# cv-strip.net
KiCad netlist of a schematic drawn in EAGLE
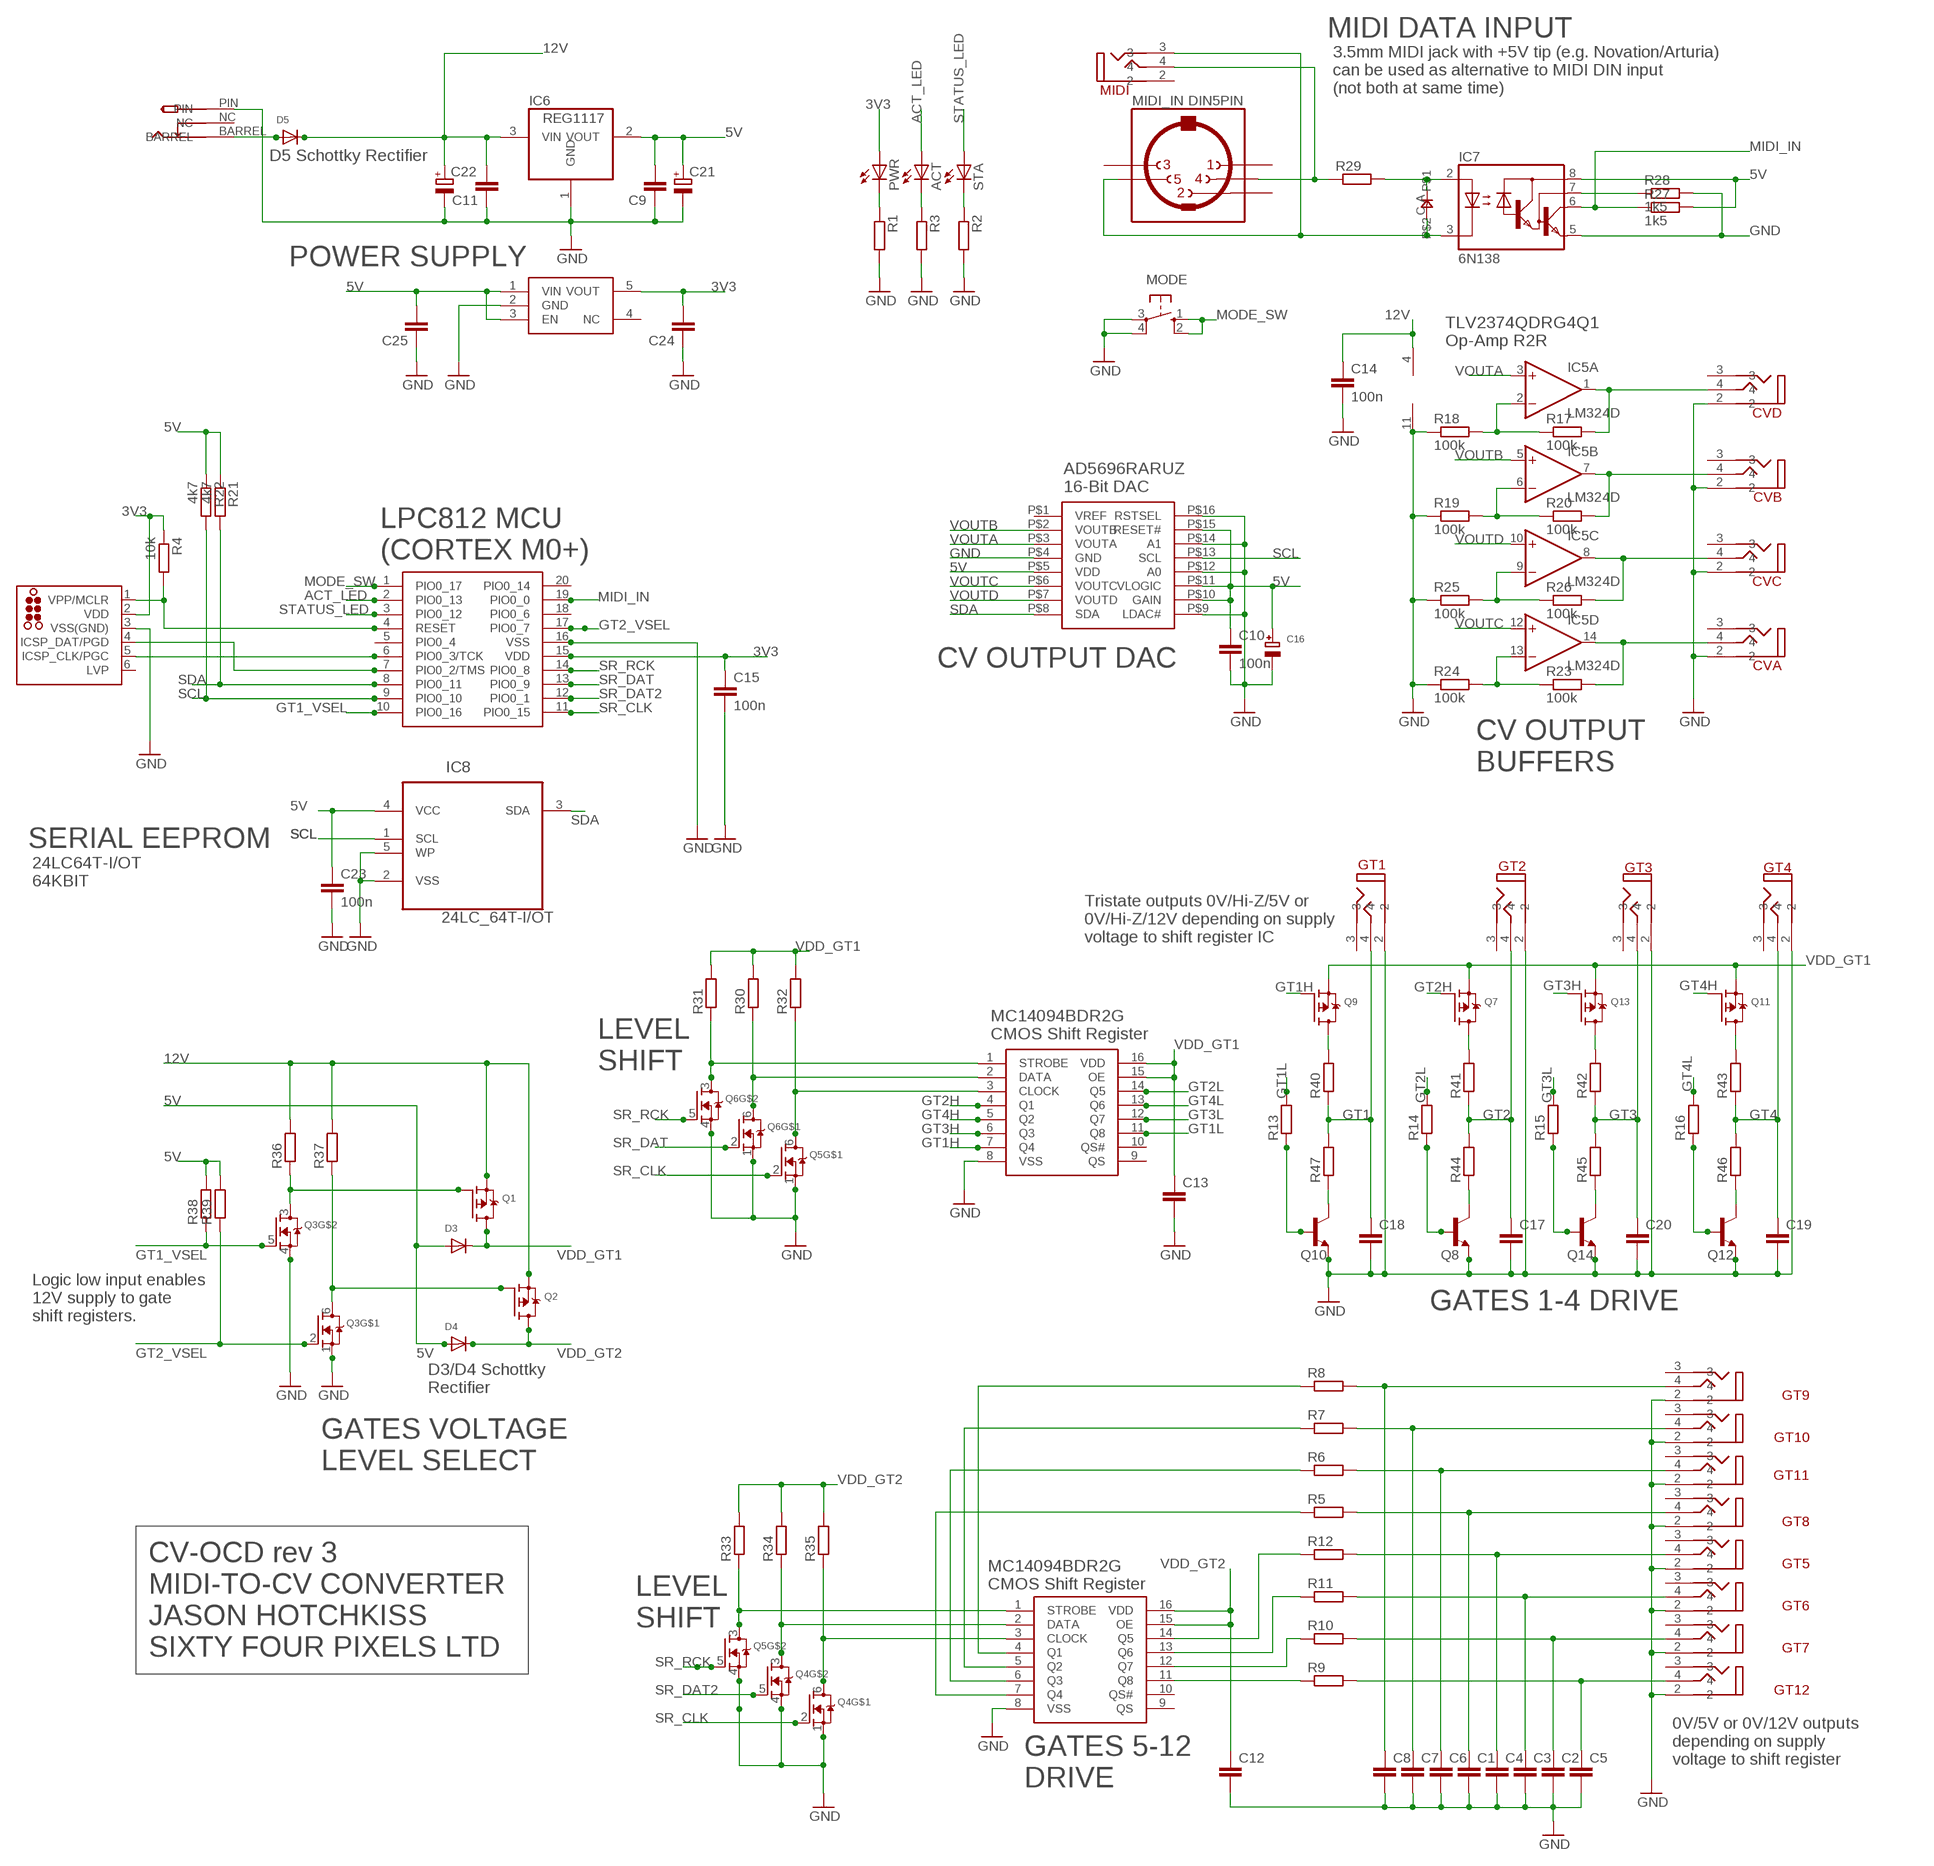
[diagram p0: schematic, sheet 1]

(export (version "E")
  (design (tool "Eeschema 10.0.6"))
  (components
    (comp (ref "ACT")
      (value "LED3MM")
      (footprint "eagle-import:LED3MM")
      (libsource (lib "eagle-import") (part "LED3MM"))
    )
    (comp (ref "C1")
      (value "C-EUC0805")
      (footprint "eagle-import:C0805")
      (libsource (lib "eagle-import") (part "C-EUC0805"))
    )
    (comp (ref "C2")
      (value "C-EUC0805")
      (footprint "eagle-import:C0805")
      (libsource (lib "eagle-import") (part "C-EUC0805"))
    )
    (comp (ref "C3")
      (value "C-EUC0805")
      (footprint "eagle-import:C0805")
      (libsource (lib "eagle-import") (part "C-EUC0805"))
    )
    (comp (ref "C4")
      (value "C-EUC0805")
      (footprint "eagle-import:C0805")
      (libsource (lib "eagle-import") (part "C-EUC0805"))
    )
    (comp (ref "C5")
      (value "C-EUC0805")
      (footprint "eagle-import:C0805")
      (libsource (lib "eagle-import") (part "C-EUC0805"))
    )
    (comp (ref "C6")
      (value "C-EUC0805")
      (footprint "eagle-import:C0805")
      (libsource (lib "eagle-import") (part "C-EUC0805"))
    )
    (comp (ref "C7")
      (value "C-EUC0805")
      (footprint "eagle-import:C0805")
      (libsource (lib "eagle-import") (part "C-EUC0805"))
    )
    (comp (ref "C8")
      (value "C-EUC0805")
      (footprint "eagle-import:C0805")
      (libsource (lib "eagle-import") (part "C-EUC0805"))
    )
    (comp (ref "C9")
      (value "C-EUC0805")
      (footprint "eagle-import:C0805")
      (libsource (lib "eagle-import") (part "C-EUC0805"))
    )
    (comp (ref "C10")
      (value "100n")
      (footprint "eagle-import:C0805")
      (libsource (lib "eagle-import") (part "C-EUC0805"))
    )
    (comp (ref "C11")
      (value "C-EUC0805")
      (footprint "eagle-import:C0805")
      (libsource (lib "eagle-import") (part "C-EUC0805"))
    )
    (comp (ref "C12")
      (value "C-EUC0805")
      (footprint "eagle-import:C0805")
      (libsource (lib "eagle-import") (part "C-EUC0805"))
    )
    (comp (ref "C13")
      (value "C-EUC0805")
      (footprint "eagle-import:C0805")
      (libsource (lib "eagle-import") (part "C-EUC0805"))
    )
    (comp (ref "C14")
      (value "100n")
      (footprint "eagle-import:C0805")
      (libsource (lib "eagle-import") (part "C-EUC0805"))
    )
    (comp (ref "C15")
      (value "100n")
      (footprint "eagle-import:C0805")
      (libsource (lib "eagle-import") (part "C-EUC0805"))
    )
    (comp (ref "C16")
      (value "CAP_TANTALUMA/3216_REFLOW")
      (footprint "eagle-import:EIA3216-18_A-R")
      (libsource (lib "eagle-import") (part "CAP_TANTALUMA/3216_REFLOW"))
    )
    (comp (ref "C17")
      (value "C-EUC0805")
      (footprint "eagle-import:C0805")
      (libsource (lib "eagle-import") (part "C-EUC0805"))
    )
    (comp (ref "C18")
      (value "C-EUC0805")
      (footprint "eagle-import:C0805")
      (libsource (lib "eagle-import") (part "C-EUC0805"))
    )
    (comp (ref "C19")
      (value "C-EUC0805")
      (footprint "eagle-import:C0805")
      (libsource (lib "eagle-import") (part "C-EUC0805"))
    )
    (comp (ref "C20")
      (value "C-EUC0805")
      (footprint "eagle-import:C0805")
      (libsource (lib "eagle-import") (part "C-EUC0805"))
    )
    (comp (ref "C21")
      (value "CPOL-EUE2.5-5")
      (footprint "eagle-import:E2,5-5")
      (libsource (lib "eagle-import") (part "CPOL-EUE2.5-5"))
    )
    (comp (ref "C22")
      (value "CPOL-EUE2.5-5")
      (footprint "eagle-import:E2,5-5")
      (libsource (lib "eagle-import") (part "CPOL-EUE2.5-5"))
    )
    (comp (ref "C23")
      (value "100n")
      (footprint "eagle-import:C0805")
      (libsource (lib "eagle-import") (part "C-EUC0805"))
    )
    (comp (ref "C24")
      (value "C-EUC0805")
      (footprint "eagle-import:C0805")
      (libsource (lib "eagle-import") (part "C-EUC0805"))
    )
    (comp (ref "C25")
      (value "C-EUC0805")
      (footprint "eagle-import:C0805")
      (libsource (lib "eagle-import") (part "C-EUC0805"))
    )
    (comp (ref "CVA")
      (value "VERTICAL_3_5MM_SOCKET")
      (footprint "eagle-import:VERTICAL_3_5MM_SOCKET")
      (libsource (lib "eagle-import") (part "VERTICAL_3_5MM_SOCKET"))
    )
    (comp (ref "CVB")
      (value "VERTICAL_3_5MM_SOCKET")
      (footprint "eagle-import:VERTICAL_3_5MM_SOCKET")
      (libsource (lib "eagle-import") (part "VERTICAL_3_5MM_SOCKET"))
    )
    (comp (ref "CVC")
      (value "VERTICAL_3_5MM_SOCKET")
      (footprint "eagle-import:VERTICAL_3_5MM_SOCKET")
      (libsource (lib "eagle-import") (part "VERTICAL_3_5MM_SOCKET"))
    )
    (comp (ref "CVD")
      (value "VERTICAL_3_5MM_SOCKET")
      (footprint "eagle-import:VERTICAL_3_5MM_SOCKET")
      (libsource (lib "eagle-import") (part "VERTICAL_3_5MM_SOCKET"))
    )
    (comp (ref "D1")
      (value "0805DIODE")
      (footprint "eagle-import:0805DIODE")
      (libsource (lib "eagle-import") (part "0805DIODE"))
    )
    (comp (ref "D3")
      (value "DIODESOD-123")
      (footprint "eagle-import:SOD-123")
      (libsource (lib "eagle-import") (part "DIODESOD-123"))
    )
    (comp (ref "D4")
      (value "DIODESOD-123")
      (footprint "eagle-import:SOD-123")
      (libsource (lib "eagle-import") (part "DIODESOD-123"))
    )
    (comp (ref "D5")
      (value "DIODESOD-123")
      (footprint "eagle-import:SOD-123")
      (libsource (lib "eagle-import") (part "DIODESOD-123"))
    )
    (comp (ref "GT1")
      (value "VERTICAL_3_5MM_SOCKET")
      (footprint "eagle-import:VERTICAL_3_5MM_SOCKET")
      (libsource (lib "eagle-import") (part "VERTICAL_3_5MM_SOCKET"))
    )
    (comp (ref "GT2")
      (value "VERTICAL_3_5MM_SOCKET")
      (footprint "eagle-import:VERTICAL_3_5MM_SOCKET")
      (libsource (lib "eagle-import") (part "VERTICAL_3_5MM_SOCKET"))
    )
    (comp (ref "GT3")
      (value "VERTICAL_3_5MM_SOCKET")
      (footprint "eagle-import:VERTICAL_3_5MM_SOCKET")
      (libsource (lib "eagle-import") (part "VERTICAL_3_5MM_SOCKET"))
    )
    (comp (ref "GT4")
      (value "VERTICAL_3_5MM_SOCKET")
      (footprint "eagle-import:VERTICAL_3_5MM_SOCKET")
      (libsource (lib "eagle-import") (part "VERTICAL_3_5MM_SOCKET"))
    )
    (comp (ref "GT5")
      (value "VERTICAL_3_5MM_SOCKET")
      (footprint "eagle-import:VERTICAL_3_5MM_SOCKET")
      (libsource (lib "eagle-import") (part "VERTICAL_3_5MM_SOCKET"))
    )
    (comp (ref "GT6")
      (value "VERTICAL_3_5MM_SOCKET")
      (footprint "eagle-import:VERTICAL_3_5MM_SOCKET")
      (libsource (lib "eagle-import") (part "VERTICAL_3_5MM_SOCKET"))
    )
    (comp (ref "GT7")
      (value "VERTICAL_3_5MM_SOCKET")
      (footprint "eagle-import:VERTICAL_3_5MM_SOCKET")
      (libsource (lib "eagle-import") (part "VERTICAL_3_5MM_SOCKET"))
    )
    (comp (ref "GT8")
      (value "VERTICAL_3_5MM_SOCKET")
      (footprint "eagle-import:VERTICAL_3_5MM_SOCKET")
      (libsource (lib "eagle-import") (part "VERTICAL_3_5MM_SOCKET"))
    )
    (comp (ref "GT9")
      (value "VERTICAL_3_5MM_SOCKET")
      (footprint "eagle-import:VERTICAL_3_5MM_SOCKET")
      (libsource (lib "eagle-import") (part "VERTICAL_3_5MM_SOCKET"))
    )
    (comp (ref "GT10")
      (value "VERTICAL_3_5MM_SOCKET")
      (footprint "eagle-import:VERTICAL_3_5MM_SOCKET")
      (libsource (lib "eagle-import") (part "VERTICAL_3_5MM_SOCKET"))
    )
    (comp (ref "GT11")
      (value "VERTICAL_3_5MM_SOCKET")
      (footprint "eagle-import:VERTICAL_3_5MM_SOCKET")
      (libsource (lib "eagle-import") (part "VERTICAL_3_5MM_SOCKET"))
    )
    (comp (ref "GT12")
      (value "VERTICAL_3_5MM_SOCKET")
      (footprint "eagle-import:VERTICAL_3_5MM_SOCKET")
      (libsource (lib "eagle-import") (part "VERTICAL_3_5MM_SOCKET"))
    )
    (comp (ref "IC1")
      (value "LPC812")
      (footprint "eagle-import:TSSOP20")
      (libsource (lib "eagle-import") (part "LPC812"))
    )
    (comp (ref "IC2")
      (value "AD5696R")
      (footprint "eagle-import:SSOP16")
      (libsource (lib "eagle-import") (part "AD5696R"))
    )
    (comp (ref "IC3")
      (value "MC14094B")
      (footprint "eagle-import:SO16")
      (libsource (lib "eagle-import") (part "MC14094B"))
    )
    (comp (ref "IC4")
      (value "MC14094B")
      (footprint "eagle-import:SO16")
      (libsource (lib "eagle-import") (part "MC14094B"))
    )
    (comp (ref "IC5")
      (value "LM324D")
      (footprint "eagle-import:SO14")
      (libsource (lib "eagle-import") (part "LM324D"))
    )
    (comp (ref "IC6")
      (value "REG1117")
      (footprint "eagle-import:SOT223")
      (libsource (lib "eagle-import") (part "REG1117"))
    )
    (comp (ref "IC7")
      (value "6N138")
      (footprint "eagle-import:DIL08")
      (fields (field (name "MF") "VISHAY/TELEFUNKEN"))
      (libsource (lib "eagle-import") (part "6N138"))
    )
    (comp (ref "IC8")
      (value "24LC_64T-I/OT")
      (footprint "eagle-import:SOT95P290X145-5N")
      (fields (field (name "MPN") "24LC64T-I/OT"))
      (libsource (lib "eagle-import") (part "24LC_64T-I/OT"))
    )
    (comp (ref "IC9")
      (value "MIC5504-2.8YM5-TR")
      (footprint "eagle-import:SOT23-5")
      (libsource (lib "eagle-import") (part "MIC5504-2.8YM5-TR"))
    )
    (comp (ref "ICSP")
      (value "TC2030-MCP-NL")
      (footprint "eagle-import:TC2030-MCP-NL")
      (libsource (lib "eagle-import") (part "TC2030-MCP-NL"))
    )
    (comp (ref "MIDI")
      (value "VERTICAL_3_5MM_SOCKET")
      (footprint "eagle-import:VERTICAL_3_5MM_SOCKET")
      (libsource (lib "eagle-import") (part "VERTICAL_3_5MM_SOCKET"))
    )
    (comp (ref "MIDI_IN")
      (value "DIN5PIN")
      (footprint "eagle-import:EDGEDIN")
      (libsource (lib "eagle-import") (part "DIN5PIN"))
    )
    (comp (ref "MODE")
      (value "10-XX")
      (footprint "eagle-import:B3F-10XX")
      (fields (field (name "MPN") "B3F-1000"))
      (libsource (lib "eagle-import") (part "10-XX"))
    )
    (comp (ref "PWR")
      (value "LED3MM")
      (footprint "eagle-import:LED3MM")
      (libsource (lib "eagle-import") (part "LED3MM"))
    )
    (comp (ref "Q1")
      (value "MOSFET-P")
      (footprint "eagle-import:SOT23-R")
      (libsource (lib "eagle-import") (part "MOSFET-P"))
    )
    (comp (ref "Q2")
      (value "MOSFET-P")
      (footprint "eagle-import:SOT23-R")
      (libsource (lib "eagle-import") (part "MOSFET-P"))
    )
    (comp (ref "Q3")
      (value "MOSFET-N_DUAL")
      (footprint "eagle-import:SOT363")
      (libsource (lib "eagle-import") (part "MOSFET-N_DUAL"))
    )
    (comp (ref "Q4")
      (value "MOSFET-N_DUAL")
      (footprint "eagle-import:SOT363")
      (libsource (lib "eagle-import") (part "MOSFET-N_DUAL"))
    )
    (comp (ref "Q5")
      (value "MOSFET-N_DUAL")
      (footprint "eagle-import:SOT363")
      (libsource (lib "eagle-import") (part "MOSFET-N_DUAL"))
    )
    (comp (ref "Q6")
      (value "MOSFET-N_DUAL")
      (footprint "eagle-import:SOT363")
      (libsource (lib "eagle-import") (part "MOSFET-N_DUAL"))
    )
    (comp (ref "Q7")
      (value "MOSFET-P")
      (footprint "eagle-import:SOT23-R")
      (libsource (lib "eagle-import") (part "MOSFET-P"))
    )
    (comp (ref "Q8")
      (value "MMBT3904LT1-NPN-SOT23-BEC")
      (footprint "eagle-import:SOT23-BEC")
      (libsource (lib "eagle-import") (part "-NPN-SOT23-BECMMBT3904LT1"))
    )
    (comp (ref "Q9")
      (value "MOSFET-P")
      (footprint "eagle-import:SOT23-R")
      (libsource (lib "eagle-import") (part "MOSFET-P"))
    )
    (comp (ref "Q10")
      (value "MMBT3904LT1-NPN-SOT23-BEC")
      (footprint "eagle-import:SOT23-BEC")
      (libsource (lib "eagle-import") (part "-NPN-SOT23-BECMMBT3904LT1"))
    )
    (comp (ref "Q11")
      (value "MOSFET-P")
      (footprint "eagle-import:SOT23-R")
      (libsource (lib "eagle-import") (part "MOSFET-P"))
    )
    (comp (ref "Q12")
      (value "MMBT3904LT1-NPN-SOT23-BEC")
      (footprint "eagle-import:SOT23-BEC")
      (libsource (lib "eagle-import") (part "-NPN-SOT23-BECMMBT3904LT1"))
    )
    (comp (ref "Q13")
      (value "MOSFET-P")
      (footprint "eagle-import:SOT23-R")
      (libsource (lib "eagle-import") (part "MOSFET-P"))
    )
    (comp (ref "Q14")
      (value "MMBT3904LT1-NPN-SOT23-BEC")
      (footprint "eagle-import:SOT23-BEC")
      (libsource (lib "eagle-import") (part "-NPN-SOT23-BECMMBT3904LT1"))
    )
    (comp (ref "R1")
      (value "R-EU_R0805")
      (footprint "eagle-import:R0805")
      (libsource (lib "eagle-import") (part "R-EU_R0805"))
    )
    (comp (ref "R2")
      (value "R-EU_R0805")
      (footprint "eagle-import:R0805")
      (libsource (lib "eagle-import") (part "R-EU_R0805"))
    )
    (comp (ref "R3")
      (value "R-EU_R0805")
      (footprint "eagle-import:R0805")
      (libsource (lib "eagle-import") (part "R-EU_R0805"))
    )
    (comp (ref "R4")
      (value "10k")
      (footprint "eagle-import:R0805")
      (libsource (lib "eagle-import") (part "R-EU_R0805"))
    )
    (comp (ref "R5")
      (value "R-EU_R0805")
      (footprint "eagle-import:R0805")
      (libsource (lib "eagle-import") (part "R-EU_R0805"))
    )
    (comp (ref "R6")
      (value "R-EU_R0805")
      (footprint "eagle-import:R0805")
      (libsource (lib "eagle-import") (part "R-EU_R0805"))
    )
    (comp (ref "R7")
      (value "R-EU_R0805")
      (footprint "eagle-import:R0805")
      (libsource (lib "eagle-import") (part "R-EU_R0805"))
    )
    (comp (ref "R8")
      (value "R-EU_R0805")
      (footprint "eagle-import:R0805")
      (libsource (lib "eagle-import") (part "R-EU_R0805"))
    )
    (comp (ref "R9")
      (value "R-EU_R0805")
      (footprint "eagle-import:R0805")
      (libsource (lib "eagle-import") (part "R-EU_R0805"))
    )
    (comp (ref "R10")
      (value "R-EU_R0805")
      (footprint "eagle-import:R0805")
      (libsource (lib "eagle-import") (part "R-EU_R0805"))
    )
    (comp (ref "R11")
      (value "R-EU_R0805")
      (footprint "eagle-import:R0805")
      (libsource (lib "eagle-import") (part "R-EU_R0805"))
    )
    (comp (ref "R12")
      (value "R-EU_R0805")
      (footprint "eagle-import:R0805")
      (libsource (lib "eagle-import") (part "R-EU_R0805"))
    )
    (comp (ref "R13")
      (value "R-EU_R0805")
      (footprint "eagle-import:R0805")
      (libsource (lib "eagle-import") (part "R-EU_R0805"))
    )
    (comp (ref "R14")
      (value "R-EU_R0805")
      (footprint "eagle-import:R0805")
      (libsource (lib "eagle-import") (part "R-EU_R0805"))
    )
    (comp (ref "R15")
      (value "R-EU_R0805")
      (footprint "eagle-import:R0805")
      (libsource (lib "eagle-import") (part "R-EU_R0805"))
    )
    (comp (ref "R16")
      (value "R-EU_R0805")
      (footprint "eagle-import:R0805")
      (libsource (lib "eagle-import") (part "R-EU_R0805"))
    )
    (comp (ref "R17")
      (value "100k")
      (footprint "eagle-import:R0805")
      (libsource (lib "eagle-import") (part "R-EU_R0805"))
    )
    (comp (ref "R18")
      (value "100k")
      (footprint "eagle-import:R0805")
      (libsource (lib "eagle-import") (part "R-EU_R0805"))
    )
    (comp (ref "R19")
      (value "100k")
      (footprint "eagle-import:R0805")
      (libsource (lib "eagle-import") (part "R-EU_R0805"))
    )
    (comp (ref "R20")
      (value "100k")
      (footprint "eagle-import:R0805")
      (libsource (lib "eagle-import") (part "R-EU_R0805"))
    )
    (comp (ref "R21")
      (value "4k7")
      (footprint "eagle-import:R0805")
      (libsource (lib "eagle-import") (part "R-EU_R0805"))
    )
    (comp (ref "R22")
      (value "4k7")
      (footprint "eagle-import:R0805")
      (libsource (lib "eagle-import") (part "R-EU_R0805"))
    )
    (comp (ref "R23")
      (value "100k")
      (footprint "eagle-import:R0805")
      (libsource (lib "eagle-import") (part "R-EU_R0805"))
    )
    (comp (ref "R24")
      (value "100k")
      (footprint "eagle-import:R0805")
      (libsource (lib "eagle-import") (part "R-EU_R0805"))
    )
    (comp (ref "R25")
      (value "100k")
      (footprint "eagle-import:R0805")
      (libsource (lib "eagle-import") (part "R-EU_R0805"))
    )
    (comp (ref "R26")
      (value "100k")
      (footprint "eagle-import:R0805")
      (libsource (lib "eagle-import") (part "R-EU_R0805"))
    )
    (comp (ref "R27")
      (value "1k5")
      (footprint "eagle-import:R0805")
      (libsource (lib "eagle-import") (part "R-EU_R0805"))
    )
    (comp (ref "R28")
      (value "1k5")
      (footprint "eagle-import:R0805")
      (libsource (lib "eagle-import") (part "R-EU_R0805"))
    )
    (comp (ref "R29")
      (value "R-EU_R0805")
      (footprint "eagle-import:R0805")
      (libsource (lib "eagle-import") (part "R-EU_R0805"))
    )
    (comp (ref "R30")
      (value "R-EU_R0805")
      (footprint "eagle-import:R0805")
      (libsource (lib "eagle-import") (part "R-EU_R0805"))
    )
    (comp (ref "R31")
      (value "R-EU_R0805")
      (footprint "eagle-import:R0805")
      (libsource (lib "eagle-import") (part "R-EU_R0805"))
    )
    (comp (ref "R32")
      (value "R-EU_R0805")
      (footprint "eagle-import:R0805")
      (libsource (lib "eagle-import") (part "R-EU_R0805"))
    )
    (comp (ref "R33")
      (value "R-EU_R0805")
      (footprint "eagle-import:R0805")
      (libsource (lib "eagle-import") (part "R-EU_R0805"))
    )
    (comp (ref "R34")
      (value "R-EU_R0805")
      (footprint "eagle-import:R0805")
      (libsource (lib "eagle-import") (part "R-EU_R0805"))
    )
    (comp (ref "R35")
      (value "R-EU_R0805")
      (footprint "eagle-import:R0805")
      (libsource (lib "eagle-import") (part "R-EU_R0805"))
    )
    (comp (ref "R36")
      (value "R-EU_R0805")
      (footprint "eagle-import:R0805")
      (libsource (lib "eagle-import") (part "R-EU_R0805"))
    )
    (comp (ref "R37")
      (value "R-EU_R0805")
      (footprint "eagle-import:R0805")
      (libsource (lib "eagle-import") (part "R-EU_R0805"))
    )
    (comp (ref "R38")
      (value "R-EU_R0805")
      (footprint "eagle-import:R0805")
      (libsource (lib "eagle-import") (part "R-EU_R0805"))
    )
    (comp (ref "R39")
      (value "R-EU_R0805")
      (footprint "eagle-import:R0805")
      (libsource (lib "eagle-import") (part "R-EU_R0805"))
    )
    (comp (ref "R40")
      (value "R-EU_R0805")
      (footprint "eagle-import:R0805")
      (libsource (lib "eagle-import") (part "R-EU_R0805"))
    )
    (comp (ref "R41")
      (value "R-EU_R0805")
      (footprint "eagle-import:R0805")
      (libsource (lib "eagle-import") (part "R-EU_R0805"))
    )
    (comp (ref "R42")
      (value "R-EU_R0805")
      (footprint "eagle-import:R0805")
      (libsource (lib "eagle-import") (part "R-EU_R0805"))
    )
    (comp (ref "R43")
      (value "R-EU_R0805")
      (footprint "eagle-import:R0805")
      (libsource (lib "eagle-import") (part "R-EU_R0805"))
    )
    (comp (ref "R44")
      (value "R-EU_R0805")
      (footprint "eagle-import:R0805")
      (libsource (lib "eagle-import") (part "R-EU_R0805"))
    )
    (comp (ref "R45")
      (value "R-EU_R0805")
      (footprint "eagle-import:R0805")
      (libsource (lib "eagle-import") (part "R-EU_R0805"))
    )
    (comp (ref "R46")
      (value "R-EU_R0805")
      (footprint "eagle-import:R0805")
      (libsource (lib "eagle-import") (part "R-EU_R0805"))
    )
    (comp (ref "R47")
      (value "R-EU_R0805")
      (footprint "eagle-import:R0805")
      (libsource (lib "eagle-import") (part "R-EU_R0805"))
    )
    (comp (ref "STA")
      (value "LED3MM")
      (footprint "eagle-import:LED3MM")
      (libsource (lib "eagle-import") (part "LED3MM"))
    )
    (comp (ref "U$2")
      (value "PWR_SOCKET_2_1MM")
      (footprint "eagle-import:PWR_SOCKET_2_1MM")
      (libsource (lib "eagle-import") (part "PWR_SOCKET_2_1MM"))
    )
  )
  (nets
    (net (code "1") (name "/3V3") (class "Default")
      (node (ref "C15") (pin "1") (pinfunction "1_1") (pintype "passive"))
      (node (ref "C24") (pin "2") (pinfunction "2_2") (pintype "passive"))
      (node (ref "IC1") (pin "15") (pinfunction "VDD_15") (pintype "bidirectional"))
      (node (ref "IC9") (pin "5") (pinfunction "VOUT_5") (pintype "output"))
      (node (ref "ICSP") (pin "2") (pinfunction "VDD_2") (pintype "power_in"))
      (node (ref "PWR") (pin "A") (pinfunction "A_A") (pintype "passive"))
      (node (ref "R4") (pin "1") (pinfunction "1_1") (pintype "passive"))
    )
    (net (code "2") (name "/5V") (class "Default")
      (node (ref "C10") (pin "1") (pinfunction "1_1") (pintype "passive"))
      (node (ref "C16") (pin "+") (pinfunction "+_+") (pintype "passive"))
      (node (ref "C21") (pin "+") (pinfunction "+_+") (pintype "passive"))
      (node (ref "C23") (pin "1") (pinfunction "1_1") (pintype "passive"))
      (node (ref "C25") (pin "2") (pinfunction "2_2") (pintype "passive"))
      (node (ref "C9") (pin "2") (pinfunction "2_2") (pintype "passive"))
      (node (ref "D3") (pin "A") (pinfunction "A_A") (pintype "passive"))
      (node (ref "D4") (pin "A") (pinfunction "A_A") (pintype "passive"))
      (node (ref "IC2") (pin "P$10") (pinfunction "GAIN_P$10") (pintype "bidirectional"))
      (node (ref "IC2") (pin "P$11") (pinfunction "VLOGIC_P$11") (pintype "power_in"))
      (node (ref "IC2") (pin "P$15") (pinfunction "RESET#_P$15") (pintype "bidirectional"))
      (node (ref "IC2") (pin "P$5") (pinfunction "VDD_P$5") (pintype "power_in"))
      (node (ref "IC6") (pin "2") (pinfunction "VOUT_2") (pintype "output"))
      (node (ref "IC7") (pin "8") (pinfunction "VCC_8") (pintype "passive"))
      (node (ref "IC8") (pin "4") (pinfunction "VCC_4") (pintype "power_in"))
      (node (ref "IC9") (pin "1") (pinfunction "VIN_1") (pintype "power_in"))
      (node (ref "IC9") (pin "3") (pinfunction "EN_3") (pintype "bidirectional"))
      (node (ref "R21") (pin "1") (pinfunction "1_1") (pintype "passive"))
      (node (ref "R22") (pin "1") (pinfunction "1_1") (pintype "passive"))
      (node (ref "R27") (pin "2") (pinfunction "2_2") (pintype "passive"))
      (node (ref "R38") (pin "2") (pinfunction "2_2") (pintype "passive"))
      (node (ref "R39") (pin "2") (pinfunction "2_2") (pintype "passive"))
    )
    (net (code "3") (name "/12V") (class "Default")
      (node (ref "C11") (pin "2") (pinfunction "2_2") (pintype "passive"))
      (node (ref "C14") (pin "1") (pinfunction "1_1") (pintype "passive"))
      (node (ref "C22") (pin "+") (pinfunction "+_+") (pintype "passive"))
      (node (ref "D5") (pin "C") (pinfunction "C_C") (pintype "passive"))
      (node (ref "IC5") (pin "4") (pinfunction "V+_4") (pintype "power_in"))
      (node (ref "IC6") (pin "3") (pinfunction "VIN_3") (pintype "input"))
      (node (ref "Q1") (pin "2") (pinfunction "S_2") (pintype "passive"))
      (node (ref "Q2") (pin "2") (pinfunction "S_2") (pintype "passive"))
      (node (ref "R36") (pin "2") (pinfunction "2_2") (pintype "passive"))
      (node (ref "R37") (pin "2") (pinfunction "2_2") (pintype "passive"))
    )
    (net (code "4") (name "/ACT_LED") (class "Default")
      (node (ref "ACT") (pin "A") (pinfunction "A_A") (pintype "passive"))
      (node (ref "IC1") (pin "2") (pinfunction "PIO0_13_2") (pintype "bidirectional"))
    )
    (net (code "5") (name "/GT1") (class "Default")
      (node (ref "C18") (pin "1") (pinfunction "1_1") (pintype "passive"))
      (node (ref "GT1") (pin "4") (pinfunction "4_4") (pintype "bidirectional"))
      (node (ref "R40") (pin "1") (pinfunction "1_1") (pintype "passive"))
      (node (ref "R47") (pin "2") (pinfunction "2_2") (pintype "passive"))
    )
    (net (code "6") (name "/GT1H") (class "Default")
      (node (ref "IC3") (pin "7") (pinfunction "Q4_7") (pintype "bidirectional"))
      (node (ref "Q9") (pin "1") (pinfunction "G_1") (pintype "passive"))
    )
    (net (code "7") (name "/GT1L") (class "Default")
      (node (ref "IC3") (pin "11") (pinfunction "Q8_11") (pintype "bidirectional"))
      (node (ref "R13") (pin "2") (pinfunction "2_2") (pintype "passive"))
    )
    (net (code "8") (name "/GT1_VSEL") (class "Default")
      (node (ref "IC1") (pin "10") (pinfunction "PIO0_16_10") (pintype "bidirectional"))
      (node (ref "Q3") (pin "5") (pinfunction "G_5") (pintype "bidirectional"))
      (node (ref "R38") (pin "1") (pinfunction "1_1") (pintype "passive"))
    )
    (net (code "9") (name "/GT2") (class "Default")
      (node (ref "C17") (pin "1") (pinfunction "1_1") (pintype "passive"))
      (node (ref "GT2") (pin "4") (pinfunction "4_4") (pintype "bidirectional"))
      (node (ref "R41") (pin "1") (pinfunction "1_1") (pintype "passive"))
      (node (ref "R44") (pin "2") (pinfunction "2_2") (pintype "passive"))
    )
    (net (code "10") (name "/GT2H") (class "Default")
      (node (ref "IC3") (pin "4") (pinfunction "Q1_4") (pintype "bidirectional"))
      (node (ref "Q7") (pin "1") (pinfunction "G_1") (pintype "passive"))
    )
    (net (code "11") (name "/GT2L") (class "Default")
      (node (ref "IC3") (pin "14") (pinfunction "Q5_14") (pintype "bidirectional"))
      (node (ref "R14") (pin "2") (pinfunction "2_2") (pintype "passive"))
    )
    (net (code "12") (name "/GT2_VSEL") (class "Default")
      (node (ref "IC1") (pin "17") (pinfunction "PIO0_7_17") (pintype "bidirectional"))
      (node (ref "Q3") (pin "2") (pinfunction "G_2") (pintype "bidirectional"))
      (node (ref "R39") (pin "1") (pinfunction "1_1") (pintype "passive"))
    )
    (net (code "13") (name "/GT3") (class "Default")
      (node (ref "C20") (pin "1") (pinfunction "1_1") (pintype "passive"))
      (node (ref "GT3") (pin "4") (pinfunction "4_4") (pintype "bidirectional"))
      (node (ref "R42") (pin "1") (pinfunction "1_1") (pintype "passive"))
      (node (ref "R45") (pin "2") (pinfunction "2_2") (pintype "passive"))
    )
    (net (code "14") (name "/GT3H") (class "Default")
      (node (ref "IC3") (pin "6") (pinfunction "Q3_6") (pintype "bidirectional"))
      (node (ref "Q13") (pin "1") (pinfunction "G_1") (pintype "passive"))
    )
    (net (code "15") (name "/GT3L") (class "Default")
      (node (ref "IC3") (pin "12") (pinfunction "Q7_12") (pintype "bidirectional"))
      (node (ref "R15") (pin "2") (pinfunction "2_2") (pintype "passive"))
    )
    (net (code "16") (name "/GT4") (class "Default")
      (node (ref "C19") (pin "1") (pinfunction "1_1") (pintype "passive"))
      (node (ref "GT4") (pin "4") (pinfunction "4_4") (pintype "bidirectional"))
      (node (ref "R43") (pin "1") (pinfunction "1_1") (pintype "passive"))
      (node (ref "R46") (pin "2") (pinfunction "2_2") (pintype "passive"))
    )
    (net (code "17") (name "/GT4H") (class "Default")
      (node (ref "IC3") (pin "5") (pinfunction "Q2_5") (pintype "bidirectional"))
      (node (ref "Q11") (pin "1") (pinfunction "G_1") (pintype "passive"))
    )
    (net (code "18") (name "/GT4L") (class "Default")
      (node (ref "IC3") (pin "13") (pinfunction "Q6_13") (pintype "bidirectional"))
      (node (ref "R16") (pin "2") (pinfunction "2_2") (pintype "passive"))
    )
    (net (code "19") (name "/MIDI_IN") (class "Default")
      (node (ref "IC1") (pin "19") (pinfunction "PIO0_0_19") (pintype "bidirectional"))
      (node (ref "IC7") (pin "6") (pinfunction "VO_6") (pintype "passive"))
      (node (ref "R27") (pin "1") (pinfunction "1_1") (pintype "passive"))
    )
    (net (code "20") (name "/MODE_SW") (class "Default")
      (node (ref "IC1") (pin "1") (pinfunction "PIO0_17_1") (pintype "bidirectional"))
      (node (ref "MODE") (pin "1") (pinfunction "S_1") (pintype "passive"))
      (node (ref "MODE") (pin "2") (pinfunction "S1_2") (pintype "passive"))
    )
    (net (code "21") (name "/SCL") (class "Default")
      (node (ref "IC1") (pin "9") (pinfunction "PIO0_10_9") (pintype "bidirectional"))
      (node (ref "IC2") (pin "P$13") (pinfunction "SCL_P$13") (pintype "bidirectional"))
      (node (ref "IC8") (pin "1") (pinfunction "SCL_1") (pintype "input"))
      (node (ref "R22") (pin "2") (pinfunction "2_2") (pintype "passive"))
    )
    (net (code "22") (name "/SDA") (class "Default")
      (node (ref "IC1") (pin "8") (pinfunction "PIO0_11_8") (pintype "bidirectional"))
      (node (ref "IC2") (pin "P$8") (pinfunction "SDA_P$8") (pintype "bidirectional"))
      (node (ref "IC8") (pin "3") (pinfunction "SDA_3") (pintype "bidirectional"))
      (node (ref "R21") (pin "2") (pinfunction "2_2") (pintype "passive"))
    )
    (net (code "23") (name "/SR_CLK") (class "Default")
      (node (ref "IC1") (pin "11") (pinfunction "PIO0_15_11") (pintype "bidirectional"))
      (node (ref "Q4") (pin "2") (pinfunction "G_2") (pintype "bidirectional"))
      (node (ref "Q5") (pin "2") (pinfunction "G_2") (pintype "bidirectional"))
    )
    (net (code "24") (name "/SR_DAT") (class "Default")
      (node (ref "IC1") (pin "13") (pinfunction "PIO0_9_13") (pintype "bidirectional"))
      (node (ref "Q6") (pin "2") (pinfunction "G_2") (pintype "bidirectional"))
    )
    (net (code "25") (name "/SR_DAT2") (class "Default")
      (node (ref "IC1") (pin "12") (pinfunction "PIO0_1_12") (pintype "bidirectional"))
      (node (ref "Q4") (pin "5") (pinfunction "G_5") (pintype "bidirectional"))
    )
    (net (code "26") (name "/SR_RCK") (class "Default")
      (node (ref "IC1") (pin "14") (pinfunction "PIO0_8_14") (pintype "bidirectional"))
      (node (ref "Q5") (pin "5") (pinfunction "G_5") (pintype "bidirectional"))
      (node (ref "Q6") (pin "5") (pinfunction "G_5") (pintype "bidirectional"))
    )
    (net (code "27") (name "/STATUS_LED") (class "Default")
      (node (ref "IC1") (pin "3") (pinfunction "PIO0_12_3") (pintype "bidirectional"))
      (node (ref "STA") (pin "A") (pinfunction "A_A") (pintype "passive"))
    )
    (net (code "28") (name "/VDD_GT1") (class "Default")
      (node (ref "C13") (pin "1") (pinfunction "1_1") (pintype "passive"))
      (node (ref "D3") (pin "C") (pinfunction "C_C") (pintype "passive"))
      (node (ref "IC3") (pin "15") (pinfunction "OE_15") (pintype "bidirectional"))
      (node (ref "IC3") (pin "16") (pinfunction "VDD_16") (pintype "power_in"))
      (node (ref "Q1") (pin "3") (pinfunction "D_3") (pintype "passive"))
      (node (ref "Q11") (pin "2") (pinfunction "S_2") (pintype "passive"))
      (node (ref "Q13") (pin "2") (pinfunction "S_2") (pintype "passive"))
      (node (ref "Q7") (pin "2") (pinfunction "S_2") (pintype "passive"))
      (node (ref "Q9") (pin "2") (pinfunction "S_2") (pintype "passive"))
      (node (ref "R30") (pin "2") (pinfunction "2_2") (pintype "passive"))
      (node (ref "R31") (pin "2") (pinfunction "2_2") (pintype "passive"))
      (node (ref "R32") (pin "2") (pinfunction "2_2") (pintype "passive"))
    )
    (net (code "29") (name "/VDD_GT2") (class "Default")
      (node (ref "C12") (pin "1") (pinfunction "1_1") (pintype "passive"))
      (node (ref "D4") (pin "C") (pinfunction "C_C") (pintype "passive"))
      (node (ref "IC4") (pin "15") (pinfunction "OE_15") (pintype "bidirectional"))
      (node (ref "IC4") (pin "16") (pinfunction "VDD_16") (pintype "power_in"))
      (node (ref "Q2") (pin "3") (pinfunction "D_3") (pintype "passive"))
      (node (ref "R33") (pin "2") (pinfunction "2_2") (pintype "passive"))
      (node (ref "R34") (pin "2") (pinfunction "2_2") (pintype "passive"))
      (node (ref "R35") (pin "2") (pinfunction "2_2") (pintype "passive"))
    )
    (net (code "30") (name "/VOUTA") (class "Default")
      (node (ref "IC2") (pin "P$3") (pinfunction "VOUTA_P$3") (pintype "bidirectional"))
      (node (ref "IC5") (pin "3") (pinfunction "+IN_3") (pintype "input"))
    )
    (net (code "31") (name "/VOUTB") (class "Default")
      (node (ref "IC2") (pin "P$2") (pinfunction "VOUTB_P$2") (pintype "bidirectional"))
      (node (ref "IC5") (pin "5") (pinfunction "+IN_5") (pintype "input"))
    )
    (net (code "32") (name "/VOUTC") (class "Default")
      (node (ref "IC2") (pin "P$6") (pinfunction "VOUTC_P$6") (pintype "bidirectional"))
      (node (ref "IC5") (pin "12") (pinfunction "+IN_12") (pintype "input"))
    )
    (net (code "33") (name "/VOUTD") (class "Default")
      (node (ref "IC2") (pin "P$7") (pinfunction "VOUTD_P$7") (pintype "bidirectional"))
      (node (ref "IC5") (pin "10") (pinfunction "+IN_10") (pintype "input"))
    )
    (net (code "34") (name "GND") (class "Default")
      (node (ref "C1") (pin "2") (pinfunction "2_2") (pintype "passive"))
      (node (ref "C10") (pin "2") (pinfunction "2_2") (pintype "passive"))
      (node (ref "C11") (pin "1") (pinfunction "1_1") (pintype "passive"))
      (node (ref "C12") (pin "2") (pinfunction "2_2") (pintype "passive"))
      (node (ref "C13") (pin "2") (pinfunction "2_2") (pintype "passive"))
      (node (ref "C14") (pin "2") (pinfunction "2_2") (pintype "passive"))
      (node (ref "C15") (pin "2") (pinfunction "2_2") (pintype "passive"))
      (node (ref "C16") (pin "-") (pinfunction "-_-") (pintype "passive"))
      (node (ref "C17") (pin "2") (pinfunction "2_2") (pintype "passive"))
      (node (ref "C18") (pin "2") (pinfunction "2_2") (pintype "passive"))
      (node (ref "C19") (pin "2") (pinfunction "2_2") (pintype "passive"))
      (node (ref "C2") (pin "2") (pinfunction "2_2") (pintype "passive"))
      (node (ref "C20") (pin "2") (pinfunction "2_2") (pintype "passive"))
      (node (ref "C21") (pin "-") (pinfunction "-_-") (pintype "passive"))
      (node (ref "C22") (pin "-") (pinfunction "-_-") (pintype "passive"))
      (node (ref "C23") (pin "2") (pinfunction "2_2") (pintype "passive"))
      (node (ref "C24") (pin "1") (pinfunction "1_1") (pintype "passive"))
      (node (ref "C25") (pin "1") (pinfunction "1_1") (pintype "passive"))
      (node (ref "C3") (pin "2") (pinfunction "2_2") (pintype "passive"))
      (node (ref "C4") (pin "2") (pinfunction "2_2") (pintype "passive"))
      (node (ref "C5") (pin "2") (pinfunction "2_2") (pintype "passive"))
      (node (ref "C6") (pin "2") (pinfunction "2_2") (pintype "passive"))
      (node (ref "C7") (pin "2") (pinfunction "2_2") (pintype "passive"))
      (node (ref "C8") (pin "2") (pinfunction "2_2") (pintype "passive"))
      (node (ref "C9") (pin "1") (pinfunction "1_1") (pintype "passive"))
      (node (ref "CVA") (pin "2") (pinfunction "2_2") (pintype "bidirectional"))
      (node (ref "CVB") (pin "2") (pinfunction "2_2") (pintype "bidirectional"))
      (node (ref "CVC") (pin "2") (pinfunction "2_2") (pintype "bidirectional"))
      (node (ref "CVD") (pin "2") (pinfunction "2_2") (pintype "bidirectional"))
      (node (ref "GT1") (pin "2") (pinfunction "2_2") (pintype "bidirectional"))
      (node (ref "GT10") (pin "2") (pinfunction "2_2") (pintype "bidirectional"))
      (node (ref "GT11") (pin "2") (pinfunction "2_2") (pintype "bidirectional"))
      (node (ref "GT12") (pin "2") (pinfunction "2_2") (pintype "bidirectional"))
      (node (ref "GT2") (pin "2") (pinfunction "2_2") (pintype "bidirectional"))
      (node (ref "GT3") (pin "2") (pinfunction "2_2") (pintype "bidirectional"))
      (node (ref "GT4") (pin "2") (pinfunction "2_2") (pintype "bidirectional"))
      (node (ref "GT5") (pin "2") (pinfunction "2_2") (pintype "bidirectional"))
      (node (ref "GT6") (pin "2") (pinfunction "2_2") (pintype "bidirectional"))
      (node (ref "GT7") (pin "2") (pinfunction "2_2") (pintype "bidirectional"))
      (node (ref "GT8") (pin "2") (pinfunction "2_2") (pintype "bidirectional"))
      (node (ref "GT9") (pin "2") (pinfunction "2_2") (pintype "bidirectional"))
      (node (ref "IC1") (pin "16") (pinfunction "VSS_16") (pintype "bidirectional"))
      (node (ref "IC2") (pin "P$12") (pinfunction "A0_P$12") (pintype "bidirectional"))
      (node (ref "IC2") (pin "P$14") (pinfunction "A1_P$14") (pintype "bidirectional"))
      (node (ref "IC2") (pin "P$16") (pinfunction "RSTSEL_P$16") (pintype "bidirectional"))
      (node (ref "IC2") (pin "P$4") (pinfunction "GND_P$4") (pintype "power_in"))
      (node (ref "IC2") (pin "P$9") (pinfunction "LDAC#_P$9") (pintype "bidirectional"))
      (node (ref "IC3") (pin "8") (pinfunction "VSS_8") (pintype "power_in"))
      (node (ref "IC4") (pin "8") (pinfunction "VSS_8") (pintype "power_in"))
      (node (ref "IC5") (pin "11") (pinfunction "V-_11") (pintype "power_in"))
      (node (ref "IC6") (pin "1") (pinfunction "GND_1") (pintype "power_in"))
      (node (ref "IC7") (pin "5") (pinfunction "GND_5") (pintype "passive"))
      (node (ref "IC8") (pin "2") (pinfunction "VSS_2") (pintype "passive"))
      (node (ref "IC8") (pin "5") (pinfunction "WP_5") (pintype "input"))
      (node (ref "IC9") (pin "2") (pinfunction "GND_2") (pintype "power_in"))
      (node (ref "ICSP") (pin "3") (pinfunction "VSS(GND)_3") (pintype "power_in"))
      (node (ref "MODE") (pin "3") (pinfunction "P_3") (pintype "passive"))
      (node (ref "MODE") (pin "4") (pinfunction "P1_4") (pintype "passive"))
      (node (ref "Q10") (pin "E") (pinfunction "E_E") (pintype "passive"))
      (node (ref "Q12") (pin "E") (pinfunction "E_E") (pintype "passive"))
      (node (ref "Q14") (pin "E") (pinfunction "E_E") (pintype "passive"))
      (node (ref "Q3") (pin "1") (pinfunction "S_1") (pintype "bidirectional"))
      (node (ref "Q3") (pin "4") (pinfunction "S_4") (pintype "bidirectional"))
      (node (ref "Q4") (pin "1") (pinfunction "S_1") (pintype "bidirectional"))
      (node (ref "Q4") (pin "4") (pinfunction "S_4") (pintype "bidirectional"))
      (node (ref "Q5") (pin "1") (pinfunction "S_1") (pintype "bidirectional"))
      (node (ref "Q5") (pin "4") (pinfunction "S_4") (pintype "bidirectional"))
      (node (ref "Q6") (pin "1") (pinfunction "S_1") (pintype "bidirectional"))
      (node (ref "Q6") (pin "4") (pinfunction "S_4") (pintype "bidirectional"))
      (node (ref "Q8") (pin "E") (pinfunction "E_E") (pintype "passive"))
      (node (ref "R1") (pin "2") (pinfunction "2_2") (pintype "passive"))
      (node (ref "R18") (pin "1") (pinfunction "1_1") (pintype "passive"))
      (node (ref "R19") (pin "1") (pinfunction "1_1") (pintype "passive"))
      (node (ref "R2") (pin "2") (pinfunction "2_2") (pintype "passive"))
      (node (ref "R24") (pin "1") (pinfunction "1_1") (pintype "passive"))
      (node (ref "R25") (pin "1") (pinfunction "1_1") (pintype "passive"))
      (node (ref "R28") (pin "2") (pinfunction "2_2") (pintype "passive"))
      (node (ref "R3") (pin "2") (pinfunction "2_2") (pintype "passive"))
      (node (ref "U$2") (pin "PIN") (pinfunction "PIN_PIN") (pintype "bidirectional"))
    )
    (net (code "35") (name "Net-(ACT-C)") (class "Default")
      (node (ref "ACT") (pin "K") (pinfunction "C_K") (pintype "passive"))
      (node (ref "R3") (pin "1") (pinfunction "1_1") (pintype "passive"))
    )
    (net (code "36") (name "Net-(C1-Pad1)") (class "Default")
      (node (ref "C1") (pin "1") (pinfunction "1_1") (pintype "passive"))
      (node (ref "GT8") (pin "4") (pinfunction "4_4") (pintype "bidirectional"))
      (node (ref "R5") (pin "2") (pinfunction "2_2") (pintype "passive"))
    )
    (net (code "37") (name "Net-(C2-Pad1)") (class "Default")
      (node (ref "C2") (pin "1") (pinfunction "1_1") (pintype "passive"))
      (node (ref "GT7") (pin "4") (pinfunction "4_4") (pintype "bidirectional"))
      (node (ref "R10") (pin "2") (pinfunction "2_2") (pintype "passive"))
    )
    (net (code "38") (name "Net-(C3-Pad1)") (class "Default")
      (node (ref "C3") (pin "1") (pinfunction "1_1") (pintype "passive"))
      (node (ref "GT6") (pin "4") (pinfunction "4_4") (pintype "bidirectional"))
      (node (ref "R11") (pin "2") (pinfunction "2_2") (pintype "passive"))
    )
    (net (code "39") (name "Net-(C4-Pad1)") (class "Default")
      (node (ref "C4") (pin "1") (pinfunction "1_1") (pintype "passive"))
      (node (ref "GT5") (pin "4") (pinfunction "4_4") (pintype "bidirectional"))
      (node (ref "R12") (pin "2") (pinfunction "2_2") (pintype "passive"))
    )
    (net (code "40") (name "Net-(C5-Pad1)") (class "Default")
      (node (ref "C5") (pin "1") (pinfunction "1_1") (pintype "passive"))
      (node (ref "GT12") (pin "4") (pinfunction "4_4") (pintype "bidirectional"))
      (node (ref "R9") (pin "2") (pinfunction "2_2") (pintype "passive"))
    )
    (net (code "41") (name "Net-(C6-Pad1)") (class "Default")
      (node (ref "C6") (pin "1") (pinfunction "1_1") (pintype "passive"))
      (node (ref "GT11") (pin "4") (pinfunction "4_4") (pintype "bidirectional"))
      (node (ref "R6") (pin "2") (pinfunction "2_2") (pintype "passive"))
    )
    (net (code "42") (name "Net-(C7-Pad1)") (class "Default")
      (node (ref "C7") (pin "1") (pinfunction "1_1") (pintype "passive"))
      (node (ref "GT10") (pin "4") (pinfunction "4_4") (pintype "bidirectional"))
      (node (ref "R7") (pin "2") (pinfunction "2_2") (pintype "passive"))
    )
    (net (code "43") (name "Net-(C8-Pad1)") (class "Default")
      (node (ref "C8") (pin "1") (pinfunction "1_1") (pintype "passive"))
      (node (ref "GT9") (pin "4") (pinfunction "4_4") (pintype "bidirectional"))
      (node (ref "R8") (pin "2") (pinfunction "2_2") (pintype "passive"))
    )
    (net (code "44") (name "Net-(D1-P$1)") (class "Default")
      (node (ref "D1") (pin "C") (pinfunction "P$1_C") (pintype "bidirectional"))
      (node (ref "IC7") (pin "3") (pinfunction "C_3") (pintype "passive"))
      (node (ref "MIDI") (pin "3") (pinfunction "3_3") (pintype "bidirectional"))
      (node (ref "MIDI_IN") (pin "5") (pinfunction "5_5") (pintype "passive"))
    )
    (net (code "45") (name "Net-(D1-P$2)") (class "Default")
      (node (ref "D1") (pin "A") (pinfunction "P$2_A") (pintype "bidirectional"))
      (node (ref "IC7") (pin "2") (pinfunction "A_2") (pintype "passive"))
      (node (ref "R29") (pin "2") (pinfunction "2_2") (pintype "passive"))
    )
    (net (code "46") (name "Net-(D5-PadA)") (class "Default")
      (node (ref "D5") (pin "A") (pinfunction "A_A") (pintype "passive"))
      (node (ref "U$2") (pin "BARREL") (pinfunction "BARREL_BARREL") (pintype "bidirectional"))
    )
    (net (code "47") (name "Net-(IC1-PIO0_2{slash}TMS)") (class "Default")
      (node (ref "IC1") (pin "7") (pinfunction "PIO0_2/TMS_7") (pintype "bidirectional"))
      (node (ref "ICSP") (pin "4") (pinfunction "ICSP_DAT/PGD_4") (pintype "bidirectional"))
    )
    (net (code "48") (name "Net-(IC1-PIO0_3{slash}TCK)") (class "Default")
      (node (ref "IC1") (pin "6") (pinfunction "PIO0_3/TCK_6") (pintype "bidirectional"))
      (node (ref "ICSP") (pin "5") (pinfunction "ICSP_CLK/PGC_5") (pintype "output"))
    )
    (net (code "49") (name "Net-(IC1-RESET)") (class "Default")
      (node (ref "IC1") (pin "4") (pinfunction "RESET_4") (pintype "bidirectional"))
      (node (ref "ICSP") (pin "1") (pinfunction "VPP/MCLR_1") (pintype "passive"))
      (node (ref "R4") (pin "2") (pinfunction "2_2") (pintype "passive"))
    )
    (net (code "50") (name "Net-(IC3-CLOCK)") (class "Default")
      (node (ref "IC3") (pin "3") (pinfunction "CLOCK_3") (pintype "bidirectional"))
      (node (ref "Q5") (pin "6") (pinfunction "D_6") (pintype "bidirectional"))
      (node (ref "R32") (pin "1") (pinfunction "1_1") (pintype "passive"))
    )
    (net (code "51") (name "Net-(IC3-DATA)") (class "Default")
      (node (ref "IC3") (pin "2") (pinfunction "DATA_2") (pintype "bidirectional"))
      (node (ref "Q6") (pin "6") (pinfunction "D_6") (pintype "bidirectional"))
      (node (ref "R30") (pin "1") (pinfunction "1_1") (pintype "passive"))
    )
    (net (code "52") (name "Net-(IC3-STROBE)") (class "Default")
      (node (ref "IC3") (pin "1") (pinfunction "STROBE_1") (pintype "bidirectional"))
      (node (ref "Q6") (pin "3") (pinfunction "D_3") (pintype "bidirectional"))
      (node (ref "R31") (pin "1") (pinfunction "1_1") (pintype "passive"))
    )
    (net (code "53") (name "Net-(IC4-CLOCK)") (class "Default")
      (node (ref "IC4") (pin "3") (pinfunction "CLOCK_3") (pintype "bidirectional"))
      (node (ref "Q4") (pin "6") (pinfunction "D_6") (pintype "bidirectional"))
      (node (ref "R35") (pin "1") (pinfunction "1_1") (pintype "passive"))
    )
    (net (code "54") (name "Net-(IC4-DATA)") (class "Default")
      (node (ref "IC4") (pin "2") (pinfunction "DATA_2") (pintype "bidirectional"))
      (node (ref "Q4") (pin "3") (pinfunction "D_3") (pintype "bidirectional"))
      (node (ref "R34") (pin "1") (pinfunction "1_1") (pintype "passive"))
    )
    (net (code "55") (name "Net-(IC4-Q1)") (class "Default")
      (node (ref "IC4") (pin "4") (pinfunction "Q1_4") (pintype "bidirectional"))
      (node (ref "R8") (pin "1") (pinfunction "1_1") (pintype "passive"))
    )
    (net (code "56") (name "Net-(IC4-Q2)") (class "Default")
      (node (ref "IC4") (pin "5") (pinfunction "Q2_5") (pintype "bidirectional"))
      (node (ref "R7") (pin "1") (pinfunction "1_1") (pintype "passive"))
    )
    (net (code "57") (name "Net-(IC4-Q3)") (class "Default")
      (node (ref "IC4") (pin "6") (pinfunction "Q3_6") (pintype "bidirectional"))
      (node (ref "R6") (pin "1") (pinfunction "1_1") (pintype "passive"))
    )
    (net (code "58") (name "Net-(IC4-Q4)") (class "Default")
      (node (ref "IC4") (pin "7") (pinfunction "Q4_7") (pintype "bidirectional"))
      (node (ref "R5") (pin "1") (pinfunction "1_1") (pintype "passive"))
    )
    (net (code "59") (name "Net-(IC4-Q5)") (class "Default")
      (node (ref "IC4") (pin "14") (pinfunction "Q5_14") (pintype "bidirectional"))
      (node (ref "R12") (pin "1") (pinfunction "1_1") (pintype "passive"))
    )
    (net (code "60") (name "Net-(IC4-Q6)") (class "Default")
      (node (ref "IC4") (pin "13") (pinfunction "Q6_13") (pintype "bidirectional"))
      (node (ref "R11") (pin "1") (pinfunction "1_1") (pintype "passive"))
    )
    (net (code "61") (name "Net-(IC4-Q7)") (class "Default")
      (node (ref "IC4") (pin "12") (pinfunction "Q7_12") (pintype "bidirectional"))
      (node (ref "R10") (pin "1") (pinfunction "1_1") (pintype "passive"))
    )
    (net (code "62") (name "Net-(IC4-Q8)") (class "Default")
      (node (ref "IC4") (pin "11") (pinfunction "Q8_11") (pintype "bidirectional"))
      (node (ref "R9") (pin "1") (pinfunction "1_1") (pintype "passive"))
    )
    (net (code "63") (name "Net-(IC4-STROBE)") (class "Default")
      (node (ref "IC4") (pin "1") (pinfunction "STROBE_1") (pintype "bidirectional"))
      (node (ref "Q5") (pin "3") (pinfunction "D_3") (pintype "bidirectional"))
      (node (ref "R33") (pin "1") (pinfunction "1_1") (pintype "passive"))
    )
    (net (code "64") (name "Net-(IC5A--IN)") (class "Default")
      (node (ref "IC5") (pin "2") (pinfunction "-IN_2") (pintype "input"))
      (node (ref "R17") (pin "1") (pinfunction "1_1") (pintype "passive"))
      (node (ref "R18") (pin "2") (pinfunction "2_2") (pintype "passive"))
    )
    (net (code "65") (name "Net-(IC5A-OUT)") (class "Default")
      (node (ref "CVD") (pin "4") (pinfunction "4_4") (pintype "bidirectional"))
      (node (ref "IC5") (pin "1") (pinfunction "OUT_1") (pintype "output"))
      (node (ref "R17") (pin "2") (pinfunction "2_2") (pintype "passive"))
    )
    (net (code "66") (name "Net-(IC5B--IN)") (class "Default")
      (node (ref "IC5") (pin "6") (pinfunction "-IN_6") (pintype "input"))
      (node (ref "R19") (pin "2") (pinfunction "2_2") (pintype "passive"))
      (node (ref "R20") (pin "1") (pinfunction "1_1") (pintype "passive"))
    )
    (net (code "67") (name "Net-(IC5B-OUT)") (class "Default")
      (node (ref "CVB") (pin "4") (pinfunction "4_4") (pintype "bidirectional"))
      (node (ref "IC5") (pin "7") (pinfunction "OUT_7") (pintype "output"))
      (node (ref "R20") (pin "2") (pinfunction "2_2") (pintype "passive"))
    )
    (net (code "68") (name "Net-(IC5C--IN)") (class "Default")
      (node (ref "IC5") (pin "9") (pinfunction "-IN_9") (pintype "input"))
      (node (ref "R25") (pin "2") (pinfunction "2_2") (pintype "passive"))
      (node (ref "R26") (pin "1") (pinfunction "1_1") (pintype "passive"))
    )
    (net (code "69") (name "Net-(IC5C-OUT)") (class "Default")
      (node (ref "CVC") (pin "4") (pinfunction "4_4") (pintype "bidirectional"))
      (node (ref "IC5") (pin "8") (pinfunction "OUT_8") (pintype "output"))
      (node (ref "R26") (pin "2") (pinfunction "2_2") (pintype "passive"))
    )
    (net (code "70") (name "Net-(IC5D--IN)") (class "Default")
      (node (ref "IC5") (pin "13") (pinfunction "-IN_13") (pintype "input"))
      (node (ref "R23") (pin "1") (pinfunction "1_1") (pintype "passive"))
      (node (ref "R24") (pin "2") (pinfunction "2_2") (pintype "passive"))
    )
    (net (code "71") (name "Net-(IC5D-OUT)") (class "Default")
      (node (ref "CVA") (pin "4") (pinfunction "4_4") (pintype "bidirectional"))
      (node (ref "IC5") (pin "14") (pinfunction "OUT_14") (pintype "output"))
      (node (ref "R23") (pin "2") (pinfunction "2_2") (pintype "passive"))
    )
    (net (code "72") (name "Net-(IC7-VB)") (class "Default")
      (node (ref "IC7") (pin "7") (pinfunction "VB_7") (pintype "passive"))
      (node (ref "R28") (pin "1") (pinfunction "1_1") (pintype "passive"))
    )
    (net (code "73") (name "Net-(MIDI-Pad4)") (class "Default")
      (node (ref "MIDI") (pin "4") (pinfunction "4_4") (pintype "bidirectional"))
      (node (ref "MIDI_IN") (pin "4") (pinfunction "4_4") (pintype "passive"))
      (node (ref "R29") (pin "1") (pinfunction "1_1") (pintype "passive"))
    )
    (net (code "74") (name "Net-(PWR-C)") (class "Default")
      (node (ref "PWR") (pin "K") (pinfunction "C_K") (pintype "passive"))
      (node (ref "R1") (pin "1") (pinfunction "1_1") (pintype "passive"))
    )
    (net (code "75") (name "Net-(Q1-G)") (class "Default")
      (node (ref "Q1") (pin "1") (pinfunction "G_1") (pintype "passive"))
      (node (ref "Q3") (pin "3") (pinfunction "D_3") (pintype "bidirectional"))
      (node (ref "R36") (pin "1") (pinfunction "1_1") (pintype "passive"))
    )
    (net (code "76") (name "Net-(Q2-G)") (class "Default")
      (node (ref "Q2") (pin "1") (pinfunction "G_1") (pintype "passive"))
      (node (ref "Q3") (pin "6") (pinfunction "D_6") (pintype "bidirectional"))
      (node (ref "R37") (pin "1") (pinfunction "1_1") (pintype "passive"))
    )
    (net (code "77") (name "Net-(Q7-D)") (class "Default")
      (node (ref "Q7") (pin "3") (pinfunction "D_3") (pintype "passive"))
      (node (ref "R41") (pin "2") (pinfunction "2_2") (pintype "passive"))
    )
    (net (code "78") (name "Net-(Q8-PadB)") (class "Default")
      (node (ref "Q8") (pin "B") (pinfunction "B_B") (pintype "passive"))
      (node (ref "R14") (pin "1") (pinfunction "1_1") (pintype "passive"))
    )
    (net (code "79") (name "Net-(Q8-PadC)") (class "Default")
      (node (ref "Q8") (pin "C") (pinfunction "C_C") (pintype "passive"))
      (node (ref "R44") (pin "1") (pinfunction "1_1") (pintype "passive"))
    )
    (net (code "80") (name "Net-(Q9-D)") (class "Default")
      (node (ref "Q9") (pin "3") (pinfunction "D_3") (pintype "passive"))
      (node (ref "R40") (pin "2") (pinfunction "2_2") (pintype "passive"))
    )
    (net (code "81") (name "Net-(Q10-PadB)") (class "Default")
      (node (ref "Q10") (pin "B") (pinfunction "B_B") (pintype "passive"))
      (node (ref "R13") (pin "1") (pinfunction "1_1") (pintype "passive"))
    )
    (net (code "82") (name "Net-(Q10-PadC)") (class "Default")
      (node (ref "Q10") (pin "C") (pinfunction "C_C") (pintype "passive"))
      (node (ref "R47") (pin "1") (pinfunction "1_1") (pintype "passive"))
    )
    (net (code "83") (name "Net-(Q11-D)") (class "Default")
      (node (ref "Q11") (pin "3") (pinfunction "D_3") (pintype "passive"))
      (node (ref "R43") (pin "2") (pinfunction "2_2") (pintype "passive"))
    )
    (net (code "84") (name "Net-(Q12-PadB)") (class "Default")
      (node (ref "Q12") (pin "B") (pinfunction "B_B") (pintype "passive"))
      (node (ref "R16") (pin "1") (pinfunction "1_1") (pintype "passive"))
    )
    (net (code "85") (name "Net-(Q12-PadC)") (class "Default")
      (node (ref "Q12") (pin "C") (pinfunction "C_C") (pintype "passive"))
      (node (ref "R46") (pin "1") (pinfunction "1_1") (pintype "passive"))
    )
    (net (code "86") (name "Net-(Q13-D)") (class "Default")
      (node (ref "Q13") (pin "3") (pinfunction "D_3") (pintype "passive"))
      (node (ref "R42") (pin "2") (pinfunction "2_2") (pintype "passive"))
    )
    (net (code "87") (name "Net-(Q14-PadB)") (class "Default")
      (node (ref "Q14") (pin "B") (pinfunction "B_B") (pintype "passive"))
      (node (ref "R15") (pin "1") (pinfunction "1_1") (pintype "passive"))
    )
    (net (code "88") (name "Net-(Q14-PadC)") (class "Default")
      (node (ref "Q14") (pin "C") (pinfunction "C_C") (pintype "passive"))
      (node (ref "R45") (pin "1") (pinfunction "1_1") (pintype "passive"))
    )
    (net (code "89") (name "Net-(STA-C)") (class "Default")
      (node (ref "R2") (pin "1") (pinfunction "1_1") (pintype "passive"))
      (node (ref "STA") (pin "K") (pinfunction "C_K") (pintype "passive"))
    )
    (net (code "90") (name "unconnected-(CVA-Pad3)") (class "Default")
      (node (ref "CVA") (pin "3") (pinfunction "3_3") (pintype "bidirectional"))
    )
    (net (code "91") (name "unconnected-(CVB-Pad3)") (class "Default")
      (node (ref "CVB") (pin "3") (pinfunction "3_3") (pintype "bidirectional"))
    )
    (net (code "92") (name "unconnected-(CVC-Pad3)") (class "Default")
      (node (ref "CVC") (pin "3") (pinfunction "3_3") (pintype "bidirectional"))
    )
    (net (code "93") (name "unconnected-(CVD-Pad3)") (class "Default")
      (node (ref "CVD") (pin "3") (pinfunction "3_3") (pintype "bidirectional"))
    )
    (net (code "94") (name "unconnected-(GT1-Pad3)") (class "Default")
      (node (ref "GT1") (pin "3") (pinfunction "3_3") (pintype "bidirectional"))
    )
    (net (code "95") (name "unconnected-(GT2-Pad3)") (class "Default")
      (node (ref "GT2") (pin "3") (pinfunction "3_3") (pintype "bidirectional"))
    )
    (net (code "96") (name "unconnected-(GT3-Pad3)") (class "Default")
      (node (ref "GT3") (pin "3") (pinfunction "3_3") (pintype "bidirectional"))
    )
    (net (code "97") (name "unconnected-(GT4-Pad3)") (class "Default")
      (node (ref "GT4") (pin "3") (pinfunction "3_3") (pintype "bidirectional"))
    )
    (net (code "98") (name "unconnected-(GT5-Pad3)") (class "Default")
      (node (ref "GT5") (pin "3") (pinfunction "3_3") (pintype "bidirectional"))
    )
    (net (code "99") (name "unconnected-(GT6-Pad3)") (class "Default")
      (node (ref "GT6") (pin "3") (pinfunction "3_3") (pintype "bidirectional"))
    )
    (net (code "100") (name "unconnected-(GT7-Pad3)") (class "Default")
      (node (ref "GT7") (pin "3") (pinfunction "3_3") (pintype "bidirectional"))
    )
    (net (code "101") (name "unconnected-(GT8-Pad3)") (class "Default")
      (node (ref "GT8") (pin "3") (pinfunction "3_3") (pintype "bidirectional"))
    )
    (net (code "102") (name "unconnected-(GT9-Pad3)") (class "Default")
      (node (ref "GT9") (pin "3") (pinfunction "3_3") (pintype "bidirectional"))
    )
    (net (code "103") (name "unconnected-(GT10-Pad3)") (class "Default")
      (node (ref "GT10") (pin "3") (pinfunction "3_3") (pintype "bidirectional"))
    )
    (net (code "104") (name "unconnected-(GT11-Pad3)") (class "Default")
      (node (ref "GT11") (pin "3") (pinfunction "3_3") (pintype "bidirectional"))
    )
    (net (code "105") (name "unconnected-(GT12-Pad3)") (class "Default")
      (node (ref "GT12") (pin "3") (pinfunction "3_3") (pintype "bidirectional"))
    )
    (net (code "106") (name "unconnected-(IC1-PIO0_4-Pad5)") (class "Default")
      (node (ref "IC1") (pin "5") (pinfunction "PIO0_4_5") (pintype "bidirectional"))
    )
    (net (code "107") (name "unconnected-(IC1-PIO0_6-Pad18)") (class "Default")
      (node (ref "IC1") (pin "18") (pinfunction "PIO0_6_18") (pintype "bidirectional"))
    )
    (net (code "108") (name "unconnected-(IC1-PIO0_14-Pad20)") (class "Default")
      (node (ref "IC1") (pin "20") (pinfunction "PIO0_14_20") (pintype "bidirectional"))
    )
    (net (code "109") (name "unconnected-(IC2-VREF-PadP$1)") (class "Default")
      (node (ref "IC2") (pin "P$1") (pinfunction "VREF_P$1") (pintype "bidirectional"))
    )
    (net (code "110") (name "unconnected-(IC3-QS#-Pad10)") (class "Default")
      (node (ref "IC3") (pin "10") (pinfunction "QS#_10") (pintype "bidirectional"))
    )
    (net (code "111") (name "unconnected-(IC3-QS-Pad9)") (class "Default")
      (node (ref "IC3") (pin "9") (pinfunction "QS_9") (pintype "bidirectional"))
    )
    (net (code "112") (name "unconnected-(IC4-QS#-Pad10)") (class "Default")
      (node (ref "IC4") (pin "10") (pinfunction "QS#_10") (pintype "bidirectional"))
    )
    (net (code "113") (name "unconnected-(IC4-QS-Pad9)") (class "Default")
      (node (ref "IC4") (pin "9") (pinfunction "QS_9") (pintype "bidirectional"))
    )
    (net (code "114") (name "unconnected-(IC9-NC-Pad4)") (class "Default")
      (node (ref "IC9") (pin "4") (pinfunction "NC_4") (pintype "no_connect"))
    )
    (net (code "115") (name "unconnected-(ICSP-LVP-Pad6)") (class "Default")
      (node (ref "ICSP") (pin "6") (pinfunction "LVP_6") (pintype "bidirectional"))
    )
    (net (code "116") (name "unconnected-(MIDI-Pad2)") (class "Default")
      (node (ref "MIDI") (pin "2") (pinfunction "2_2") (pintype "bidirectional"))
    )
    (net (code "117") (name "unconnected-(MIDI_IN-Pad1)") (class "Default")
      (node (ref "MIDI_IN") (pin "1") (pinfunction "1_1") (pintype "passive"))
    )
    (net (code "118") (name "unconnected-(MIDI_IN-Pad2)") (class "Default")
      (node (ref "MIDI_IN") (pin "2") (pinfunction "2_2") (pintype "passive"))
    )
    (net (code "119") (name "unconnected-(MIDI_IN-Pad3)") (class "Default")
      (node (ref "MIDI_IN") (pin "3") (pinfunction "3_3") (pintype "passive"))
    )
    (net (code "120") (name "unconnected-(U$2-PadNC)") (class "Default")
      (node (ref "U$2") (pin "NC") (pinfunction "NC_NC") (pintype "bidirectional"))
    )
  )
)
